# PAGE04_POWER_DECOUPLI.net
KiCad netlist of a schematic drawn in Altium Designer
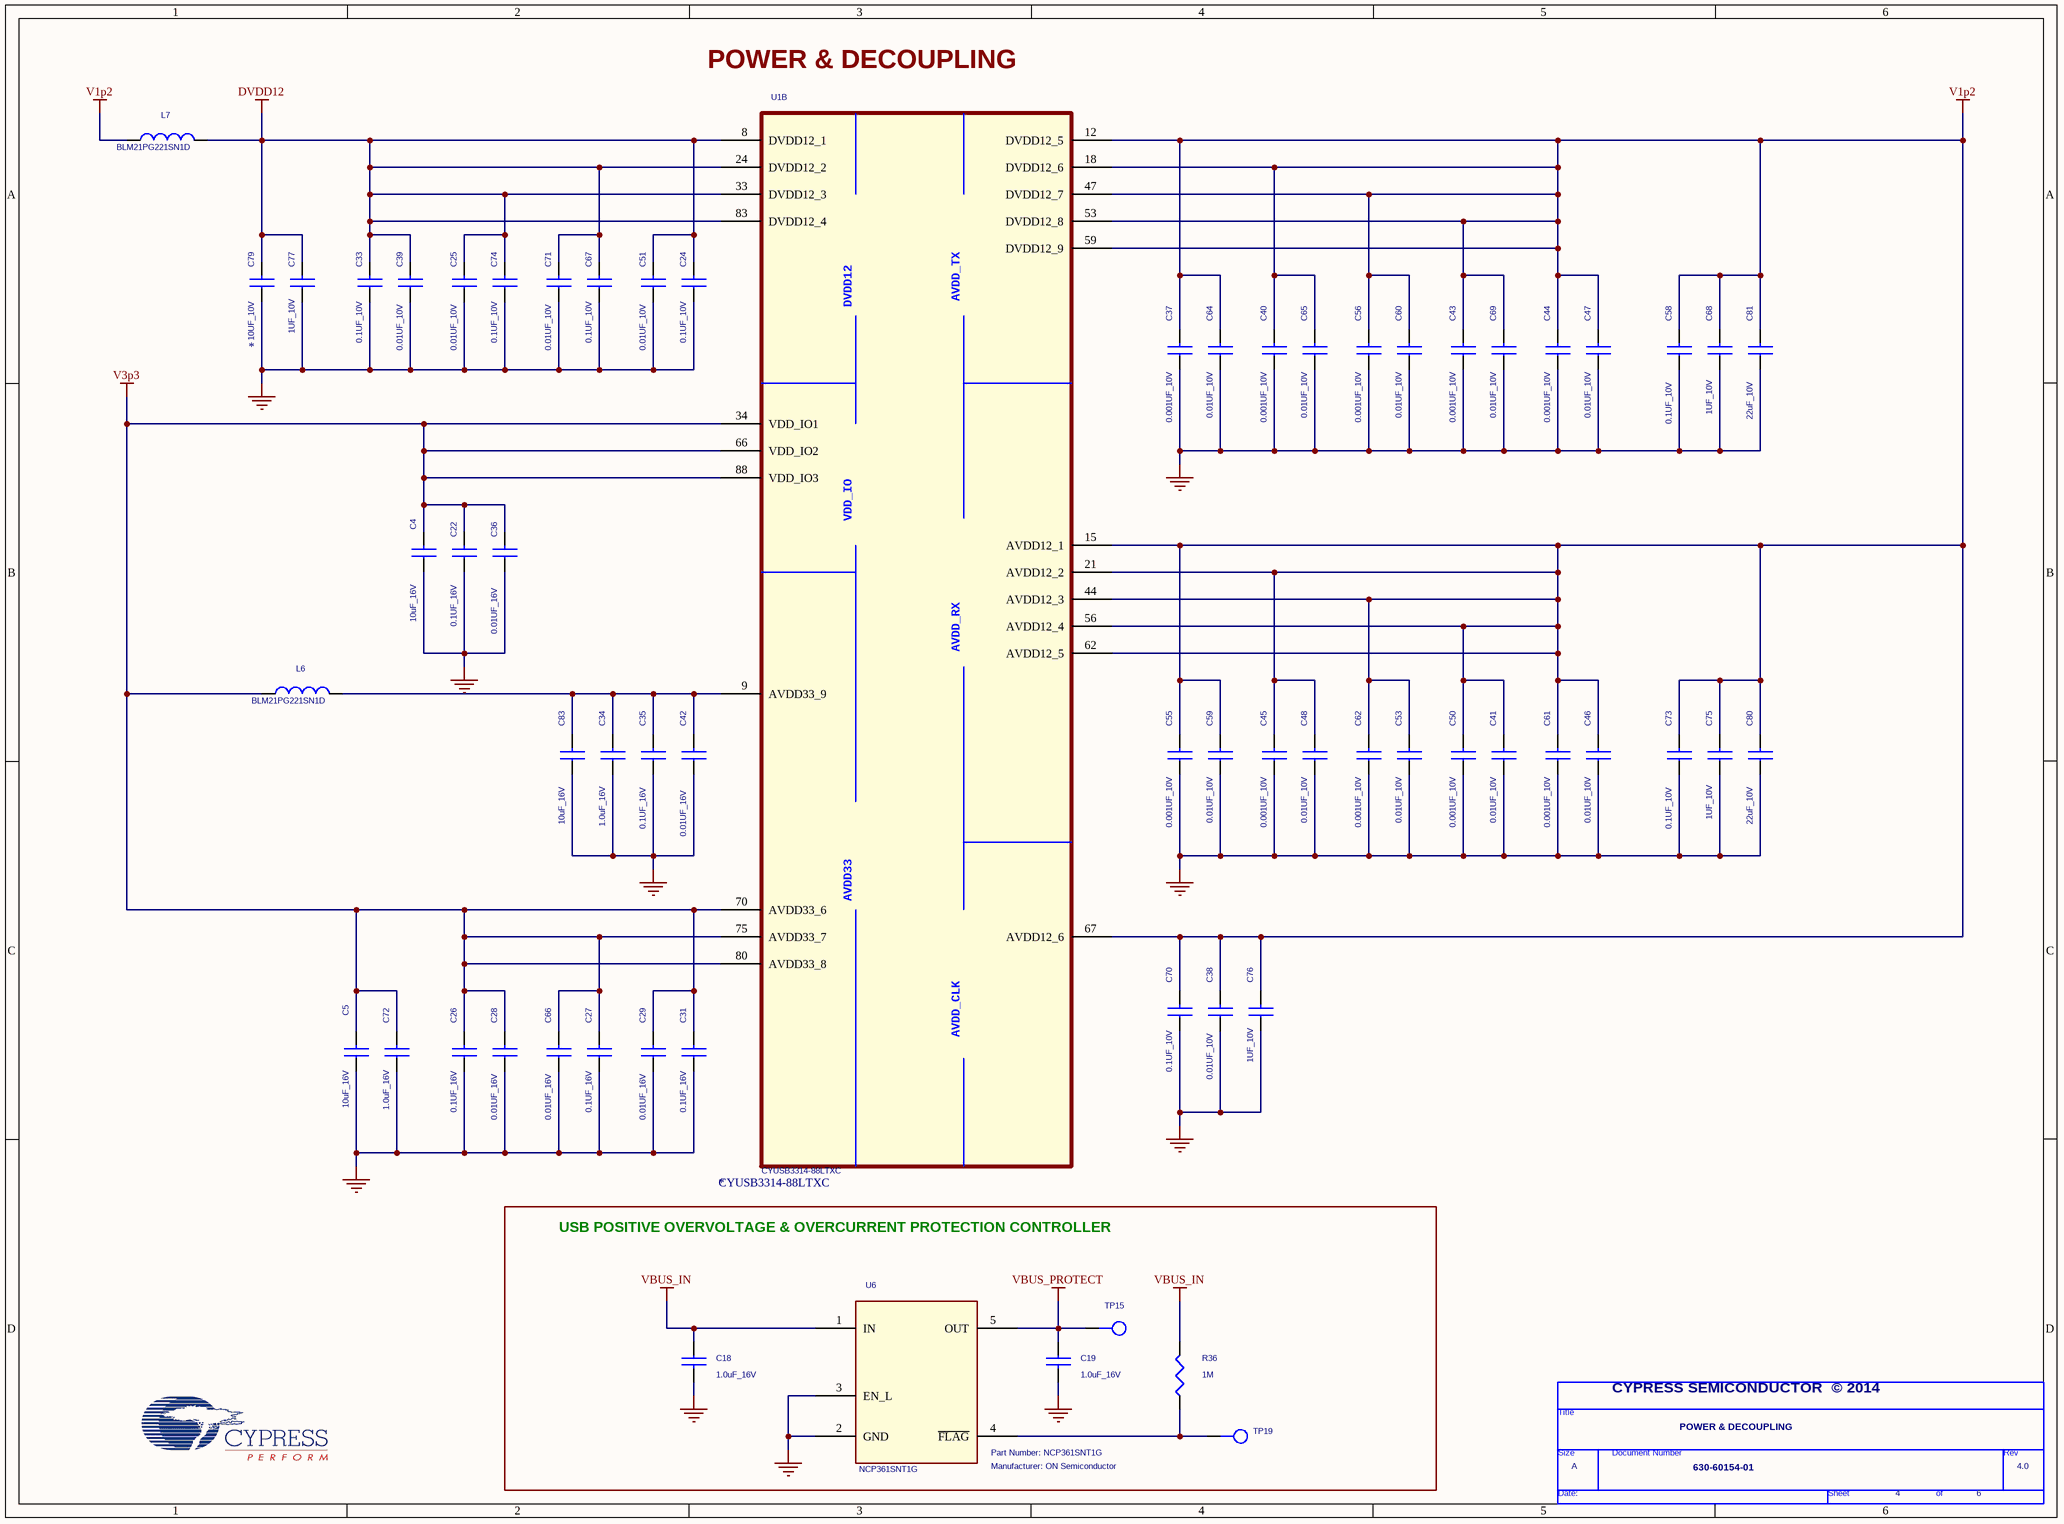
[diagram p0: PAGE04_POWER & DECOUPLI.SchDoc]

(export (version "E")
  (design (tool "Eeschema 10.0.6"))
  (components
    (comp (ref "*")
      (value "TitleBlock0")
      (fields
        (field (name "PAGE COUNT") "6")
        (field (name "PAGE NUMBER") "4")
        (field (name "PAGE SIZE") "A")
        (field (name "TITLE") "POWER & DECOUPLING")
        (field (name "REVCODE") "4.0")
        (field (name "DOC") "630-60154-01")
      )
      (libsource (lib "*") (part "TitleBlock0"))
    )
    (comp (ref "C4")
      (value "10uF_16V")
      (footprint "CAPC1608X90M")
      (libsource (lib "*") (part "CAPACITOR NON-POL"))
    )
    (comp (ref "C5")
      (value "10uF_16V")
      (footprint "CAPC1608X90M")
      (libsource (lib "*") (part "CAPACITOR NON-POL"))
    )
    (comp (ref "C18")
      (value "1.0uF_16V")
      (footprint "CAPC1608X90M")
      (description "CAP - CER, 1uF, 10V, +/-10%, X5R, 0402")
      (libsource (lib "*") (part "CAP"))
    )
    (comp (ref "C19")
      (value "1.0uF_16V")
      (footprint "CAPC1608X90M")
      (description "CAP - CER, 1uF, 10V, +/-10%, X5R, 0402")
      (libsource (lib "*") (part "CAP"))
    )
    (comp (ref "C22")
      (value "0.1UF_16V")
      (footprint "CAPC1005X56M")
      (libsource (lib "*") (part "CAPACITOR NON-POL"))
    )
    (comp (ref "C24")
      (value "0.1UF_10V")
      (footprint "CAPC1005X56M")
      (libsource (lib "*") (part "CAPACITOR NON-POL"))
    )
    (comp (ref "C25")
      (value "0.01UF_10V")
      (footprint "CAPC1005X56M")
      (libsource (lib "*") (part "CAPACITOR NON-POL"))
    )
    (comp (ref "C26")
      (value "0.1UF_16V")
      (footprint "CAPC1005X56M")
      (libsource (lib "*") (part "CAPACITOR NON-POL"))
    )
    (comp (ref "C27")
      (value "0.1UF_16V")
      (footprint "CAPC1005X56M")
      (libsource (lib "*") (part "CAPACITOR NON-POL"))
    )
    (comp (ref "C28")
      (value "0.01UF_16V")
      (footprint "CAPC1005X56M")
      (libsource (lib "*") (part "CAPACITOR NON-POL"))
    )
    (comp (ref "C29")
      (value "0.01UF_16V")
      (footprint "CAPC1005X56M")
      (libsource (lib "*") (part "CAPACITOR NON-POL"))
    )
    (comp (ref "C31")
      (value "0.1UF_16V")
      (footprint "CAPC1005X56M")
      (libsource (lib "*") (part "CAPACITOR NON-POL"))
    )
    (comp (ref "C33")
      (value "0.1UF_10V")
      (footprint "CAPC1005X56M")
      (libsource (lib "*") (part "CAPACITOR NON-POL"))
    )
    (comp (ref "C34")
      (value "1.0uF_16V")
      (footprint "CAPC1005X56M")
      (libsource (lib "*") (part "CAPACITOR NON-POL"))
    )
    (comp (ref "C35")
      (value "0.1UF_16V")
      (footprint "CAPC1005X56M")
      (libsource (lib "*") (part "CAPACITOR NON-POL"))
    )
    (comp (ref "C36")
      (value "0.01UF_16V")
      (footprint "CAPC1005X56M")
      (libsource (lib "*") (part "CAPACITOR NON-POL"))
    )
    (comp (ref "C37")
      (value "0.001UF_10V")
      (footprint "CAPC1005X56M")
      (libsource (lib "*") (part "CAPACITOR NON-POL"))
    )
    (comp (ref "C38")
      (value "0.01UF_10V")
      (footprint "CAPC1005X56M")
      (libsource (lib "*") (part "CAPACITOR NON-POL"))
    )
    (comp (ref "C39")
      (value "0.01UF_10V")
      (footprint "CAPC1005X56M")
      (libsource (lib "*") (part "CAPACITOR NON-POL"))
    )
    (comp (ref "C40")
      (value "0.001UF_10V")
      (footprint "CAPC1005X56M")
      (libsource (lib "*") (part "CAPACITOR NON-POL"))
    )
    (comp (ref "C41")
      (value "0.01UF_10V")
      (footprint "CAPC1005X56M")
      (libsource (lib "*") (part "CAPACITOR NON-POL"))
    )
    (comp (ref "C42")
      (value "0.01UF_16V")
      (footprint "CAPC1005X56M")
      (libsource (lib "*") (part "CAPACITOR NON-POL"))
    )
    (comp (ref "C43")
      (value "0.001UF_10V")
      (footprint "CAPC1005X56M")
      (libsource (lib "*") (part "CAPACITOR NON-POL"))
    )
    (comp (ref "C44")
      (value "0.001UF_10V")
      (footprint "CAPC1005X56M")
      (libsource (lib "*") (part "CAPACITOR NON-POL"))
    )
    (comp (ref "C45")
      (value "0.001UF_10V")
      (footprint "CAPC1005X56M")
      (libsource (lib "*") (part "CAPACITOR NON-POL"))
    )
    (comp (ref "C46")
      (value "0.01UF_10V")
      (footprint "CAPC1005X56M")
      (libsource (lib "*") (part "CAPACITOR NON-POL"))
    )
    (comp (ref "C47")
      (value "0.01UF_10V")
      (footprint "CAPC1005X56M")
      (libsource (lib "*") (part "CAPACITOR NON-POL"))
    )
    (comp (ref "C48")
      (value "0.01UF_10V")
      (footprint "CAPC1005X56M")
      (libsource (lib "*") (part "CAPACITOR NON-POL"))
    )
    (comp (ref "C50")
      (value "0.001UF_10V")
      (footprint "CAPC1005X56M")
      (libsource (lib "*") (part "CAPACITOR NON-POL"))
    )
    (comp (ref "C51")
      (value "0.01UF_10V")
      (footprint "CAPC1005X56M")
      (libsource (lib "*") (part "CAPACITOR NON-POL"))
    )
    (comp (ref "C53")
      (value "0.01UF_10V")
      (footprint "CAPC1005X56M")
      (libsource (lib "*") (part "CAPACITOR NON-POL"))
    )
    (comp (ref "C55")
      (value "0.001UF_10V")
      (footprint "CAPC1005X56M")
      (libsource (lib "*") (part "CAPACITOR NON-POL"))
    )
    (comp (ref "C56")
      (value "0.001UF_10V")
      (footprint "CAPC1005X56M")
      (libsource (lib "*") (part "CAPACITOR NON-POL"))
    )
    (comp (ref "C58")
      (value "0.1UF_10V")
      (footprint "CAPC1005X56M")
      (libsource (lib "*") (part "CAPACITOR NON-POL"))
    )
    (comp (ref "C59")
      (value "0.01UF_10V")
      (footprint "CAPC1005X56M")
      (libsource (lib "*") (part "CAPACITOR NON-POL"))
    )
    (comp (ref "C60")
      (value "0.01UF_10V")
      (footprint "CAPC1005X56M")
      (libsource (lib "*") (part "CAPACITOR NON-POL"))
    )
    (comp (ref "C61")
      (value "0.001UF_10V")
      (footprint "CAPC1005X56M")
      (libsource (lib "*") (part "CAPACITOR NON-POL"))
    )
    (comp (ref "C62")
      (value "0.001UF_10V")
      (footprint "CAPC1005X56M")
      (libsource (lib "*") (part "CAPACITOR NON-POL"))
    )
    (comp (ref "C64")
      (value "0.01UF_10V")
      (footprint "CAPC1005X56M")
      (libsource (lib "*") (part "CAPACITOR NON-POL"))
    )
    (comp (ref "C65")
      (value "0.01UF_10V")
      (footprint "CAPC1005X56M")
      (libsource (lib "*") (part "CAPACITOR NON-POL"))
    )
    (comp (ref "C66")
      (value "0.01UF_16V")
      (footprint "CAPC1005X56M")
      (libsource (lib "*") (part "CAPACITOR NON-POL"))
    )
    (comp (ref "C67")
      (value "0.1UF_10V")
      (footprint "CAPC1005X56M")
      (libsource (lib "*") (part "CAPACITOR NON-POL"))
    )
    (comp (ref "C68") (value "1UF_10V") (libsource (lib "*") (part "CAPACITOR NON-POL")))
    (comp (ref "C69")
      (value "0.01UF_10V")
      (footprint "CAPC1005X56M")
      (libsource (lib "*") (part "CAPACITOR NON-POL"))
    )
    (comp (ref "C70")
      (value "0.1UF_10V")
      (footprint "CAPC1005X56M")
      (libsource (lib "*") (part "CAPACITOR NON-POL"))
    )
    (comp (ref "C71")
      (value "0.01UF_10V")
      (footprint "CAPC1005X56M")
      (libsource (lib "*") (part "CAPACITOR NON-POL"))
    )
    (comp (ref "C72")
      (value "1.0uF_16V")
      (footprint "CAPC1005X56M")
      (libsource (lib "*") (part "CAPACITOR NON-POL"))
    )
    (comp (ref "C73")
      (value "0.1UF_10V")
      (footprint "CAPC1005X56M")
      (libsource (lib "*") (part "CAPACITOR NON-POL"))
    )
    (comp (ref "C74")
      (value "0.1UF_10V")
      (footprint "CAPC1005X56M")
      (libsource (lib "*") (part "CAPACITOR NON-POL"))
    )
    (comp (ref "C75") (value "1UF_10V") (libsource (lib "*") (part "CAPACITOR NON-POL")))
    (comp (ref "C76") (value "1UF_10V") (libsource (lib "*") (part "CAPACITOR NON-POL")))
    (comp (ref "C77") (value "1UF_10V") (libsource (lib "*") (part "CAPACITOR NON-POL")))
    (comp (ref "C79")
      (value "10UF_10V")
      (footprint "CAPC1608X90M")
      (fields (field (name "MANUFACTURER") "*"))
      (libsource (lib "*") (part "CAPACITOR NON-POL"))
    )
    (comp (ref "C80") (value "22uF_10V") (libsource (lib "*") (part "CAPACITOR NON-POL")))
    (comp (ref "C81") (value "22uF_10V") (libsource (lib "*") (part "CAPACITOR NON-POL")))
    (comp (ref "C83")
      (value "10uF_16V")
      (footprint "CAPC1608X90M")
      (libsource (lib "*") (part "CAPACITOR NON-POL"))
    )
    (comp (ref "L6")
      (value "BLM21PG221SN1D")
      (description "FERRITE CHIP 220 OHM 2A 0805")
      (fields (field (name "MANUFACTURER") "Murata"))
      (libsource (lib "*") (part "INDUCTOR"))
    )
    (comp (ref "L7")
      (value "BLM21PG221SN1D")
      (description "FERRITE CHIP 220 OHM 2A 0805")
      (fields (field (name "MANUFACTURER") "Murata"))
      (libsource (lib "*") (part "INDUCTOR"))
    )
    (comp (ref "R36")
      (value "1M")
      (description "RES 1.00M OHM 1/10W 1% 0402 SMD")
      (fields (field (name "MANUFACTURER") "Panasonic") (field (name "PART NUMBER") "ERJ-2RKF1004X"))
      (libsource (lib "*") (part "R"))
    )
    (comp (ref "TP15")
      (value "TP_RED")
      (footprint "KEYSTONE_5000")
      (description "TEST POINT PC MINI .040\"D RED")
      (fields (field (name "PART_NUMBER") "5000") (field (name "MANUFACTURER") "Keystone"))
      (libsource (lib "*") (part "TP"))
    )
    (comp (ref "TP19")
      (value "TP_YEL")
      (footprint "KEYSTONE_5000")
      (description "TEST POINT PC MINI .040\"D RED")
      (fields (field (name "MANUFACTURER") "Keystone") (field (name "PART_NUMBER") "5000"))
      (libsource (lib "*") (part "TP"))
    )
    (comp (ref "U1")
      (value "CYUSB3314-88LTXC")
      (footprint "QFN40P1000X1000X100-89M")
      (fields (field (name "MANUFACTURER") "*") (field (name "PART NUMBER") "CYUSB3314-88LTXC"))
      (libsource (lib "*") (part "CYUSB3314-88LTXC_2"))
    )
    (comp (ref "U6")
      (value "NCP361SNT1G")
      (footprint "SOP95P275X110-5M")
      (description "IC USB POS OVP/OC_TSOP5")
      (fields (field (name "MANUFACTURER") "ON Semiconductor") (field (name "PART NUMBER") "NCP361SNT1G"))
      (libsource (lib "*") (part "NCP361SNT1G_0"))
    )
  )
  (nets
    (net (code "1") (name "DVDD12") (class "Default")
      (node (ref "C24") (pin "2") (pinfunction "2_2") (pintype "passive"))
      (node (ref "C25") (pin "2") (pinfunction "2_2") (pintype "passive"))
      (node (ref "C33") (pin "2") (pinfunction "2_2") (pintype "passive"))
      (node (ref "C39") (pin "2") (pinfunction "2_2") (pintype "passive"))
      (node (ref "C51") (pin "2") (pinfunction "2_2") (pintype "passive"))
      (node (ref "C67") (pin "2") (pinfunction "2_2") (pintype "passive"))
      (node (ref "C71") (pin "2") (pinfunction "2_2") (pintype "passive"))
      (node (ref "C74") (pin "2") (pinfunction "2_2") (pintype "passive"))
      (node (ref "C77") (pin "2") (pinfunction "2_2") (pintype "passive"))
      (node (ref "C79") (pin "2") (pinfunction "2_2") (pintype "passive"))
      (node (ref "L7") (pin "2") (pinfunction "2_2") (pintype "passive"))
      (node (ref "U1") (pin "24") (pinfunction "DVDD12_2_24") (pintype "passive"))
      (node (ref "U1") (pin "33") (pinfunction "DVDD12_3_33") (pintype "passive"))
      (node (ref "U1") (pin "8") (pinfunction "DVDD12_1_8") (pintype "passive"))
      (node (ref "U1") (pin "83") (pinfunction "DVDD12_4_83") (pintype "passive"))
    )
    (net (code "2") (name "GND") (class "Default")
      (node (ref "C18") (pin "2") (pinfunction "2_2") (pintype "passive"))
      (node (ref "C19") (pin "2") (pinfunction "2_2") (pintype "passive"))
      (node (ref "C22") (pin "1") (pinfunction "1_1") (pintype "passive"))
      (node (ref "C24") (pin "1") (pinfunction "1_1") (pintype "passive"))
      (node (ref "C25") (pin "1") (pinfunction "1_1") (pintype "passive"))
      (node (ref "C26") (pin "1") (pinfunction "1_1") (pintype "passive"))
      (node (ref "C27") (pin "1") (pinfunction "1_1") (pintype "passive"))
      (node (ref "C28") (pin "1") (pinfunction "1_1") (pintype "passive"))
      (node (ref "C29") (pin "1") (pinfunction "1_1") (pintype "passive"))
      (node (ref "C31") (pin "1") (pinfunction "1_1") (pintype "passive"))
      (node (ref "C33") (pin "1") (pinfunction "1_1") (pintype "passive"))
      (node (ref "C34") (pin "1") (pinfunction "1_1") (pintype "passive"))
      (node (ref "C35") (pin "1") (pinfunction "1_1") (pintype "passive"))
      (node (ref "C36") (pin "1") (pinfunction "1_1") (pintype "passive"))
      (node (ref "C37") (pin "1") (pinfunction "1_1") (pintype "passive"))
      (node (ref "C38") (pin "1") (pinfunction "1_1") (pintype "passive"))
      (node (ref "C39") (pin "1") (pinfunction "1_1") (pintype "passive"))
      (node (ref "C4") (pin "1") (pinfunction "1_1") (pintype "passive"))
      (node (ref "C40") (pin "1") (pinfunction "1_1") (pintype "passive"))
      (node (ref "C41") (pin "1") (pinfunction "1_1") (pintype "passive"))
      (node (ref "C42") (pin "1") (pinfunction "1_1") (pintype "passive"))
      (node (ref "C43") (pin "1") (pinfunction "1_1") (pintype "passive"))
      (node (ref "C44") (pin "1") (pinfunction "1_1") (pintype "passive"))
      (node (ref "C45") (pin "1") (pinfunction "1_1") (pintype "passive"))
      (node (ref "C46") (pin "1") (pinfunction "1_1") (pintype "passive"))
      (node (ref "C47") (pin "1") (pinfunction "1_1") (pintype "passive"))
      (node (ref "C48") (pin "1") (pinfunction "1_1") (pintype "passive"))
      (node (ref "C5") (pin "1") (pinfunction "1_1") (pintype "passive"))
      (node (ref "C50") (pin "1") (pinfunction "1_1") (pintype "passive"))
      (node (ref "C51") (pin "1") (pinfunction "1_1") (pintype "passive"))
      (node (ref "C53") (pin "1") (pinfunction "1_1") (pintype "passive"))
      (node (ref "C55") (pin "1") (pinfunction "1_1") (pintype "passive"))
      (node (ref "C56") (pin "1") (pinfunction "1_1") (pintype "passive"))
      (node (ref "C58") (pin "1") (pinfunction "1_1") (pintype "passive"))
      (node (ref "C59") (pin "1") (pinfunction "1_1") (pintype "passive"))
      (node (ref "C60") (pin "1") (pinfunction "1_1") (pintype "passive"))
      (node (ref "C61") (pin "1") (pinfunction "1_1") (pintype "passive"))
      (node (ref "C62") (pin "1") (pinfunction "1_1") (pintype "passive"))
      (node (ref "C64") (pin "1") (pinfunction "1_1") (pintype "passive"))
      (node (ref "C65") (pin "1") (pinfunction "1_1") (pintype "passive"))
      (node (ref "C66") (pin "1") (pinfunction "1_1") (pintype "passive"))
      (node (ref "C67") (pin "1") (pinfunction "1_1") (pintype "passive"))
      (node (ref "C68") (pin "1") (pinfunction "1_1") (pintype "passive"))
      (node (ref "C69") (pin "1") (pinfunction "1_1") (pintype "passive"))
      (node (ref "C70") (pin "1") (pinfunction "1_1") (pintype "passive"))
      (node (ref "C71") (pin "1") (pinfunction "1_1") (pintype "passive"))
      (node (ref "C72") (pin "1") (pinfunction "1_1") (pintype "passive"))
      (node (ref "C73") (pin "1") (pinfunction "1_1") (pintype "passive"))
      (node (ref "C74") (pin "1") (pinfunction "1_1") (pintype "passive"))
      (node (ref "C75") (pin "1") (pinfunction "1_1") (pintype "passive"))
      (node (ref "C76") (pin "1") (pinfunction "1_1") (pintype "passive"))
      (node (ref "C77") (pin "1") (pinfunction "1_1") (pintype "passive"))
      (node (ref "C79") (pin "1") (pinfunction "1_1") (pintype "passive"))
      (node (ref "C80") (pin "1") (pinfunction "1_1") (pintype "passive"))
      (node (ref "C81") (pin "1") (pinfunction "1_1") (pintype "passive"))
      (node (ref "C83") (pin "1") (pinfunction "1_1") (pintype "passive"))
      (node (ref "U6") (pin "2") (pinfunction "GND_2") (pintype "passive"))
      (node (ref "U6") (pin "3") (pinfunction "EN_L_3") (pintype "passive"))
    )
    (net (code "3") (name "Net-(TP19-TP)") (class "Default")
      (node (ref "R36") (pin "1") (pinfunction "1_1") (pintype "passive"))
      (node (ref "TP19") (pin "1") (pinfunction "TP_1") (pintype "passive"))
      (node (ref "U6") (pin "4") (pinfunction "~{FLAG}_4") (pintype "passive"))
    )
    (net (code "4") (name "Net-(U1B-AVDD33_9)") (class "Default")
      (node (ref "C34") (pin "2") (pinfunction "2_2") (pintype "passive"))
      (node (ref "C35") (pin "2") (pinfunction "2_2") (pintype "passive"))
      (node (ref "C42") (pin "2") (pinfunction "2_2") (pintype "passive"))
      (node (ref "C83") (pin "2") (pinfunction "2_2") (pintype "passive"))
      (node (ref "L6") (pin "2") (pinfunction "2_2") (pintype "passive"))
      (node (ref "U1") (pin "9") (pinfunction "AVDD33_9_9") (pintype "passive"))
    )
    (net (code "5") (name "V1p2") (class "Default")
      (node (ref "C37") (pin "2") (pinfunction "2_2") (pintype "passive"))
      (node (ref "C38") (pin "2") (pinfunction "2_2") (pintype "passive"))
      (node (ref "C40") (pin "2") (pinfunction "2_2") (pintype "passive"))
      (node (ref "C41") (pin "2") (pinfunction "2_2") (pintype "passive"))
      (node (ref "C43") (pin "2") (pinfunction "2_2") (pintype "passive"))
      (node (ref "C44") (pin "2") (pinfunction "2_2") (pintype "passive"))
      (node (ref "C45") (pin "2") (pinfunction "2_2") (pintype "passive"))
      (node (ref "C46") (pin "2") (pinfunction "2_2") (pintype "passive"))
      (node (ref "C47") (pin "2") (pinfunction "2_2") (pintype "passive"))
      (node (ref "C48") (pin "2") (pinfunction "2_2") (pintype "passive"))
      (node (ref "C50") (pin "2") (pinfunction "2_2") (pintype "passive"))
      (node (ref "C53") (pin "2") (pinfunction "2_2") (pintype "passive"))
      (node (ref "C55") (pin "2") (pinfunction "2_2") (pintype "passive"))
      (node (ref "C56") (pin "2") (pinfunction "2_2") (pintype "passive"))
      (node (ref "C58") (pin "2") (pinfunction "2_2") (pintype "passive"))
      (node (ref "C59") (pin "2") (pinfunction "2_2") (pintype "passive"))
      (node (ref "C60") (pin "2") (pinfunction "2_2") (pintype "passive"))
      (node (ref "C61") (pin "2") (pinfunction "2_2") (pintype "passive"))
      (node (ref "C62") (pin "2") (pinfunction "2_2") (pintype "passive"))
      (node (ref "C64") (pin "2") (pinfunction "2_2") (pintype "passive"))
      (node (ref "C65") (pin "2") (pinfunction "2_2") (pintype "passive"))
      (node (ref "C68") (pin "2") (pinfunction "2_2") (pintype "passive"))
      (node (ref "C69") (pin "2") (pinfunction "2_2") (pintype "passive"))
      (node (ref "C70") (pin "2") (pinfunction "2_2") (pintype "passive"))
      (node (ref "C73") (pin "2") (pinfunction "2_2") (pintype "passive"))
      (node (ref "C75") (pin "2") (pinfunction "2_2") (pintype "passive"))
      (node (ref "C76") (pin "2") (pinfunction "2_2") (pintype "passive"))
      (node (ref "C80") (pin "2") (pinfunction "2_2") (pintype "passive"))
      (node (ref "C81") (pin "2") (pinfunction "2_2") (pintype "passive"))
      (node (ref "L7") (pin "1") (pinfunction "1_1") (pintype "passive"))
      (node (ref "U1") (pin "12") (pinfunction "DVDD12_5_12") (pintype "passive"))
      (node (ref "U1") (pin "15") (pinfunction "AVDD12_1_15") (pintype "passive"))
      (node (ref "U1") (pin "18") (pinfunction "DVDD12_6_18") (pintype "passive"))
      (node (ref "U1") (pin "21") (pinfunction "AVDD12_2_21") (pintype "passive"))
      (node (ref "U1") (pin "44") (pinfunction "AVDD12_3_44") (pintype "passive"))
      (node (ref "U1") (pin "47") (pinfunction "DVDD12_7_47") (pintype "passive"))
      (node (ref "U1") (pin "53") (pinfunction "DVDD12_8_53") (pintype "passive"))
      (node (ref "U1") (pin "56") (pinfunction "AVDD12_4_56") (pintype "passive"))
      (node (ref "U1") (pin "59") (pinfunction "DVDD12_9_59") (pintype "passive"))
      (node (ref "U1") (pin "62") (pinfunction "AVDD12_5_62") (pintype "passive"))
      (node (ref "U1") (pin "67") (pinfunction "AVDD12_6_67") (pintype "passive"))
    )
    (net (code "6") (name "V3p3") (class "Default")
      (node (ref "C22") (pin "2") (pinfunction "2_2") (pintype "passive"))
      (node (ref "C26") (pin "2") (pinfunction "2_2") (pintype "passive"))
      (node (ref "C27") (pin "2") (pinfunction "2_2") (pintype "passive"))
      (node (ref "C28") (pin "2") (pinfunction "2_2") (pintype "passive"))
      (node (ref "C29") (pin "2") (pinfunction "2_2") (pintype "passive"))
      (node (ref "C31") (pin "2") (pinfunction "2_2") (pintype "passive"))
      (node (ref "C36") (pin "2") (pinfunction "2_2") (pintype "passive"))
      (node (ref "C4") (pin "2") (pinfunction "2_2") (pintype "passive"))
      (node (ref "C5") (pin "2") (pinfunction "2_2") (pintype "passive"))
      (node (ref "C66") (pin "2") (pinfunction "2_2") (pintype "passive"))
      (node (ref "C72") (pin "2") (pinfunction "2_2") (pintype "passive"))
      (node (ref "L6") (pin "1") (pinfunction "1_1") (pintype "passive"))
      (node (ref "U1") (pin "34") (pinfunction "VDD_IO1_34") (pintype "passive"))
      (node (ref "U1") (pin "66") (pinfunction "VDD_IO2_66") (pintype "passive"))
      (node (ref "U1") (pin "70") (pinfunction "AVDD33_6_70") (pintype "passive"))
      (node (ref "U1") (pin "75") (pinfunction "AVDD33_7_75") (pintype "passive"))
      (node (ref "U1") (pin "80") (pinfunction "AVDD33_8_80") (pintype "passive"))
      (node (ref "U1") (pin "88") (pinfunction "VDD_IO3_88") (pintype "passive"))
    )
    (net (code "7") (name "VBUS_IN") (class "Default")
      (node (ref "C18") (pin "1") (pinfunction "1_1") (pintype "passive"))
      (node (ref "R36") (pin "2") (pinfunction "2_2") (pintype "passive"))
      (node (ref "U6") (pin "1") (pinfunction "IN_1") (pintype "passive"))
    )
    (net (code "8") (name "VBUS_PROTECT") (class "Default")
      (node (ref "C19") (pin "1") (pinfunction "1_1") (pintype "passive"))
      (node (ref "TP15") (pin "1") (pinfunction "TP_1") (pintype "passive"))
      (node (ref "U6") (pin "5") (pinfunction "OUT_5") (pintype "passive"))
    )
  )
)
